# RTC.net
KiCad netlist of a schematic drawn in EAGLE
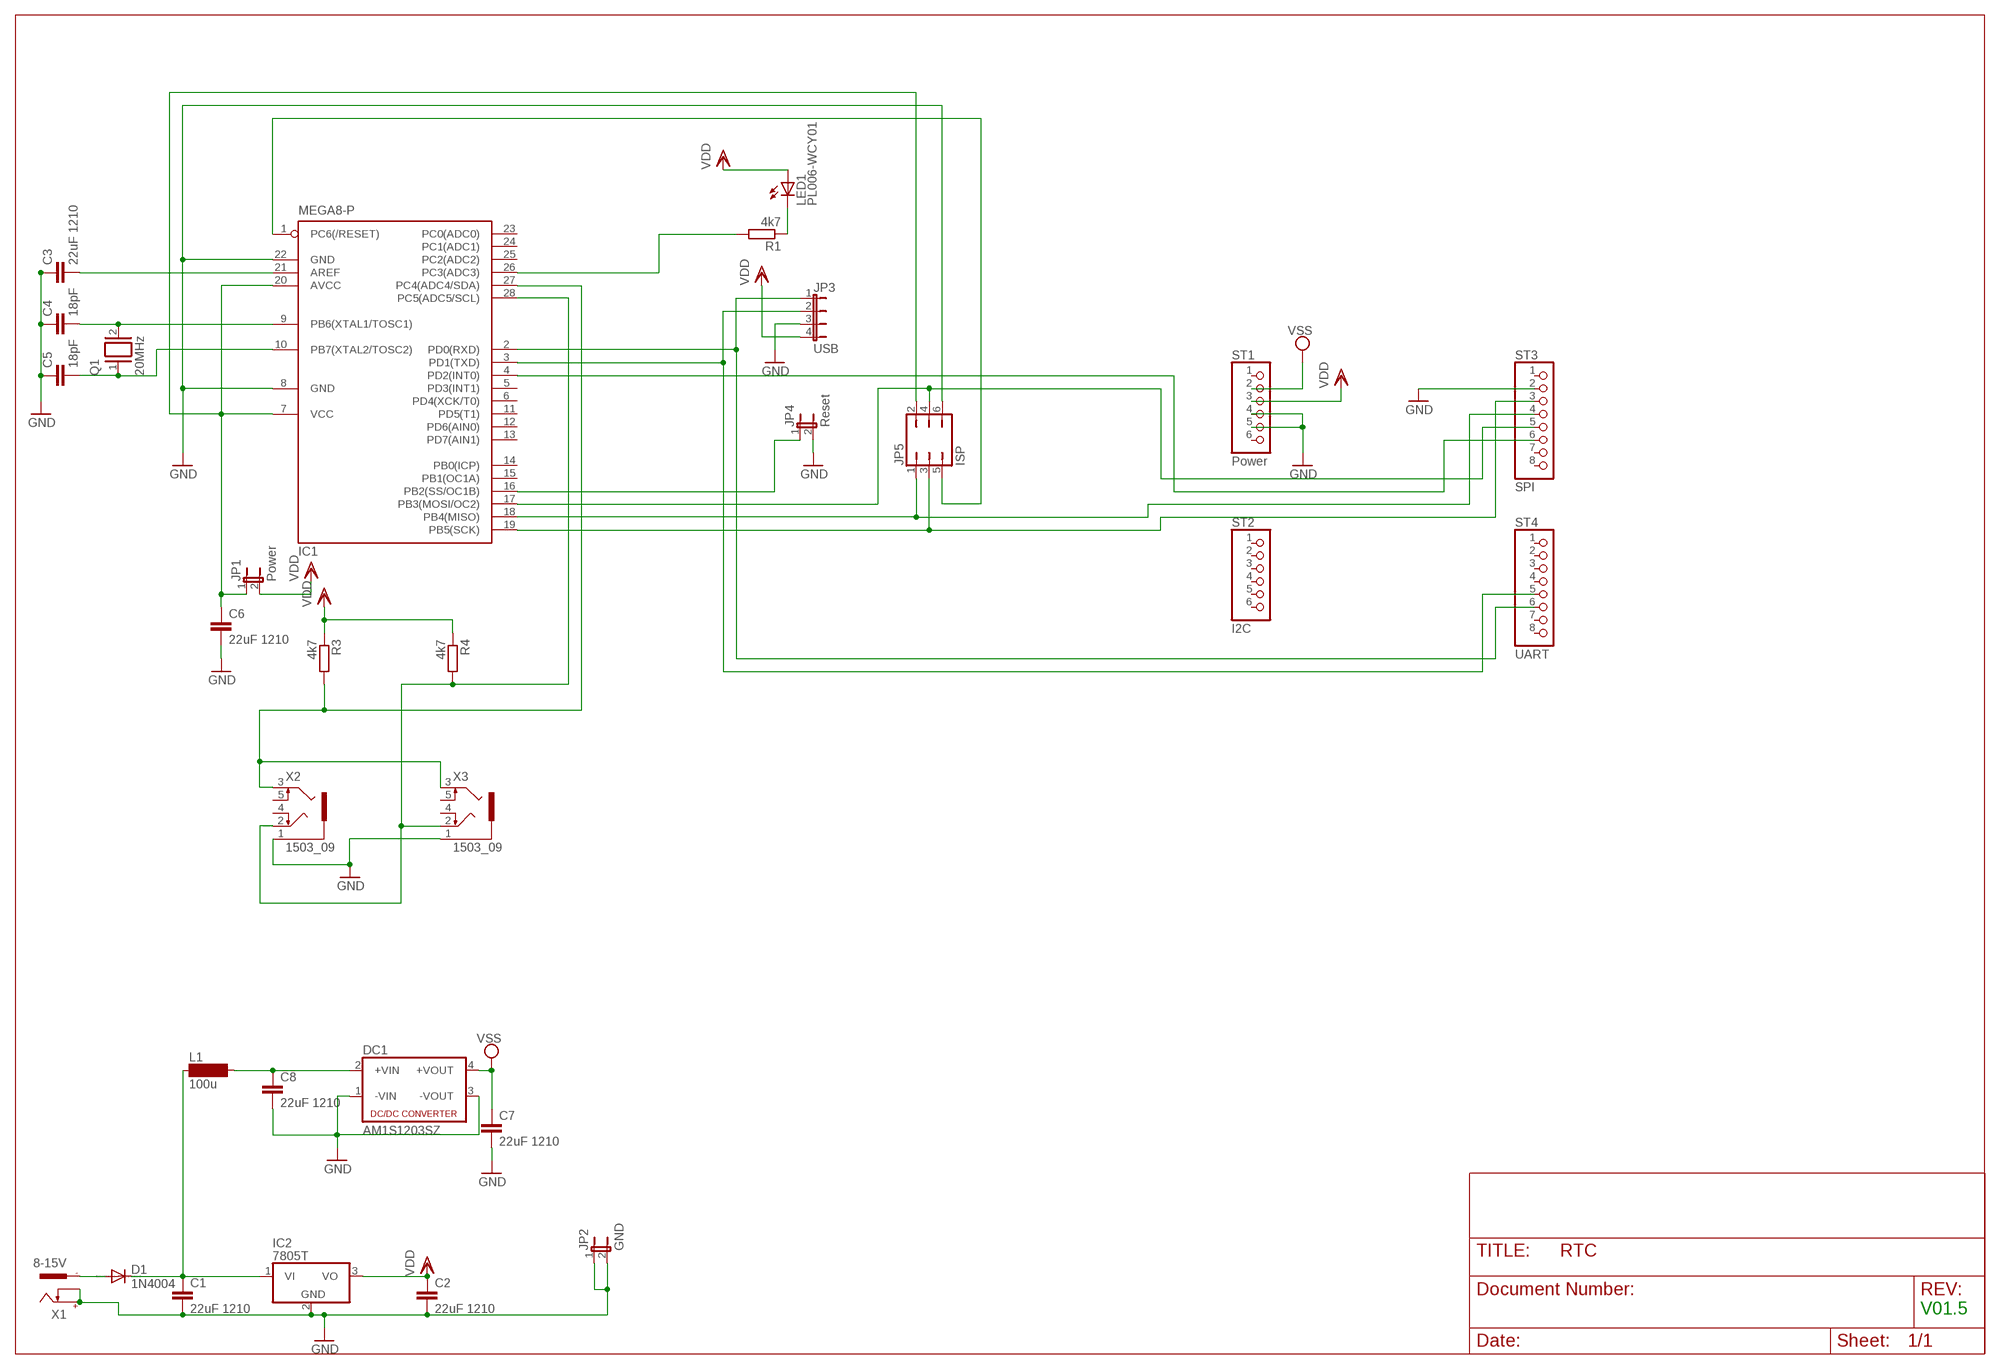
[diagram p0: schematic, sheet 1]

(export (version "E")
  (design (tool "Eeschema 10.0.6"))
  (components
    (comp (ref "C1")
      (value "22uF 1210")
      (footprint "eagle-import:C1206")
      (libsource (lib "eagle-import") (part "C-EUC1206"))
    )
    (comp (ref "C2")
      (value "22uF 1210")
      (footprint "eagle-import:C1206")
      (libsource (lib "eagle-import") (part "C-EUC1206"))
    )
    (comp (ref "C3")
      (value "22uF 1210")
      (footprint "eagle-import:C1206")
      (libsource (lib "eagle-import") (part "C-EUC1206"))
    )
    (comp (ref "C4")
      (value "18pF")
      (footprint "eagle-import:C025-025X050")
      (libsource (lib "eagle-import") (part "resistor_C-EU025-025X050"))
    )
    (comp (ref "C5")
      (value "18pF")
      (footprint "eagle-import:C025-025X050")
      (libsource (lib "eagle-import") (part "resistor_C-EU025-025X050"))
    )
    (comp (ref "C6")
      (value "22uF 1210")
      (footprint "eagle-import:C1206")
      (libsource (lib "eagle-import") (part "C-EUC1206"))
    )
    (comp (ref "C7")
      (value "22uF 1210")
      (footprint "eagle-import:C1206")
      (libsource (lib "eagle-import") (part "C-EUC1206"))
    )
    (comp (ref "C8")
      (value "22uF 1210")
      (footprint "eagle-import:C1206")
      (libsource (lib "eagle-import") (part "C-EUC1206"))
    )
    (comp (ref "D1")
      (value "1N4004")
      (footprint "eagle-import:DO41-10")
      (libsource (lib "eagle-import") (part "1N4004"))
    )
    (comp (ref "DC1")
      (value "AM1S1203SZ")
      (footprint "eagle-import:NME")
      (fields (field (name "MF") "C & D TECHNOLOGIES, INC") (field (name "MPN") "NME1205D"))
      (libsource (lib "eagle-import") (part "NME"))
    )
    (comp (ref "IC1")
      (value "MEGA8-P")
      (footprint "eagle-import:DIL28-3")
      (libsource (lib "eagle-import") (part "MEGA8-P"))
    )
    (comp (ref "IC2")
      (value "7805T")
      (footprint "eagle-import:TO220H")
      (libsource (lib "eagle-import") (part "78T05"))
    )
    (comp (ref "JP1")
      (value "Power")
      (footprint "eagle-import:JP1")
      (libsource (lib "eagle-import") (part "JP1E"))
    )
    (comp (ref "JP2")
      (value "GND")
      (footprint "eagle-import:JP1")
      (libsource (lib "eagle-import") (part "JP1E"))
    )
    (comp (ref "JP3")
      (value "USB")
      (footprint "eagle-import:JP4")
      (libsource (lib "eagle-import") (part "JP4E"))
    )
    (comp (ref "JP4")
      (value "Reset")
      (footprint "eagle-import:JP1")
      (libsource (lib "eagle-import") (part "JP1E"))
    )
    (comp (ref "JP5")
      (value "ISP")
      (footprint "eagle-import:JP3Q")
      (libsource (lib "eagle-import") (part "JP3Q"))
    )
    (comp (ref "L1")
      (value "100u")
      (footprint "eagle-import:MS85")
      (libsource (lib "eagle-import") (part "MS85"))
    )
    (comp (ref "LED1")
      (value "PL006-WCY01")
      (footprint "eagle-import:SOT23")
      (libsource (lib "eagle-import") (part "PL006-WCY01"))
    )
    (comp (ref "Q1")
      (value "20MHz")
      (footprint "eagle-import:QS")
      (libsource (lib "eagle-import") (part "XTAL/S"))
    )
    (comp (ref "R1")
      (value "4k7")
      (footprint "eagle-import:M1206")
      (libsource (lib "eagle-import") (part "R-EU_M1206"))
    )
    (comp (ref "R3")
      (value "4k7")
      (footprint "eagle-import:R1206")
      (libsource (lib "eagle-import") (part "R-EU_R1206"))
    )
    (comp (ref "R4")
      (value "4k7")
      (footprint "eagle-import:R1206")
      (libsource (lib "eagle-import") (part "R-EU_R1206"))
    )
    (comp (ref "ST1")
      (value "Power")
      (footprint "eagle-import:1X06")
      (libsource (lib "eagle-import") (part "PINHD-1X6"))
    )
    (comp (ref "ST2")
      (value "I2C")
      (footprint "eagle-import:1X06")
      (libsource (lib "eagle-import") (part "PINHD-1X6"))
    )
    (comp (ref "ST3")
      (value "SPI")
      (footprint "eagle-import:1X08")
      (libsource (lib "eagle-import") (part "PINHD-1X8"))
    )
    (comp (ref "ST4")
      (value "UART")
      (footprint "eagle-import:1X08")
      (libsource (lib "eagle-import") (part "PINHD-1X8"))
    )
    (comp (ref "X1")
      (value "8-15V")
      (footprint "eagle-import:737992-5")
      (libsource (lib "eagle-import") (part "737992-55"))
    )
    (comp (ref "X2")
      (value "1503_09")
      (footprint "eagle-import:1503_09")
      (libsource (lib "eagle-import") (part "1503_09"))
    )
    (comp (ref "X3")
      (value "1503_09")
      (footprint "eagle-import:1503_09")
      (libsource (lib "eagle-import") (part "1503_09"))
    )
  )
  (nets
    (net (code "1") (name "GND") (class "Default")
      (node (ref "C1") (pin "2") (pinfunction "2_2") (pintype "passive"))
      (node (ref "C2") (pin "2") (pinfunction "2_2") (pintype "passive"))
      (node (ref "C3") (pin "1") (pinfunction "1_1") (pintype "passive"))
      (node (ref "C4") (pin "1") (pinfunction "1_1") (pintype "passive"))
      (node (ref "C5") (pin "1") (pinfunction "1_1") (pintype "passive"))
      (node (ref "C6") (pin "2") (pinfunction "2_2") (pintype "passive"))
      (node (ref "C7") (pin "2") (pinfunction "2_2") (pintype "passive"))
      (node (ref "C8") (pin "2") (pinfunction "2_2") (pintype "passive"))
      (node (ref "DC1") (pin "1") (pinfunction "-VIN_1") (pintype "passive"))
      (node (ref "DC1") (pin "3") (pinfunction "-VOUT_3") (pintype "passive"))
      (node (ref "IC1") (pin "22") (pinfunction "GND_22") (pintype "power_in"))
      (node (ref "IC1") (pin "8") (pinfunction "GND_8") (pintype "power_in"))
      (node (ref "IC2") (pin "2") (pinfunction "GND_2") (pintype "passive"))
      (node (ref "JP2") (pin "1") (pinfunction "1_1") (pintype "passive"))
      (node (ref "JP2") (pin "2") (pinfunction "2_2") (pintype "passive"))
      (node (ref "JP3") (pin "3") (pinfunction "3_3") (pintype "passive"))
      (node (ref "JP4") (pin "2") (pinfunction "2_2") (pintype "passive"))
      (node (ref "JP5") (pin "6") (pinfunction "6_6") (pintype "passive"))
      (node (ref "ST1") (pin "4") (pinfunction "4_4") (pintype "passive"))
      (node (ref "ST1") (pin "5") (pinfunction "5_5") (pintype "passive"))
      (node (ref "ST3") (pin "2") (pinfunction "2_2") (pintype "passive"))
      (node (ref "X1") (pin "+") (pinfunction "+_+") (pintype "passive"))
      (node (ref "X1") (pin "K") (pinfunction "K_K") (pintype "passive"))
      (node (ref "X2") (pin "1") (pinfunction "1_1") (pintype "passive"))
      (node (ref "X3") (pin "1") (pinfunction "1_1") (pintype "passive"))
    )
    (net (code "2") (name "Net-(D1-PadA)") (class "Default")
      (node (ref "D1") (pin "A") (pinfunction "A_A") (pintype "passive"))
      (node (ref "X1") (pin "-1") (pinfunction "-1_-1") (pintype "passive"))
    )
    (net (code "3") (name "Net-(DC1-+VIN)") (class "Default")
      (node (ref "C8") (pin "1") (pinfunction "1_1") (pintype "passive"))
      (node (ref "DC1") (pin "2") (pinfunction "+VIN_2") (pintype "passive"))
      (node (ref "L1") (pin "2") (pinfunction "2_2") (pintype "passive"))
    )
    (net (code "4") (name "Net-(IC1-AREF)") (class "Default")
      (node (ref "C3") (pin "2") (pinfunction "2_2") (pintype "passive"))
      (node (ref "IC1") (pin "21") (pinfunction "AREF_21") (pintype "passive"))
    )
    (net (code "5") (name "Net-(IC1-AVCC)") (class "Default")
      (node (ref "C6") (pin "1") (pinfunction "1_1") (pintype "passive"))
      (node (ref "IC1") (pin "20") (pinfunction "AVCC_20") (pintype "power_in"))
      (node (ref "IC1") (pin "7") (pinfunction "VCC_7") (pintype "power_in"))
      (node (ref "JP1") (pin "1") (pinfunction "1_1") (pintype "passive"))
      (node (ref "JP5") (pin "2") (pinfunction "2_2") (pintype "passive"))
    )
    (net (code "6") (name "Net-(IC1-PB2(SS{slash}OC1B))") (class "Default")
      (node (ref "IC1") (pin "16") (pinfunction "PB2(SS/OC1B)_16") (pintype "bidirectional"))
      (node (ref "JP4") (pin "1") (pinfunction "1_1") (pintype "passive"))
    )
    (net (code "7") (name "Net-(IC1-PB3(MOSI{slash}OC2))") (class "Default")
      (node (ref "IC1") (pin "17") (pinfunction "PB3(MOSI/OC2)_17") (pintype "bidirectional"))
      (node (ref "JP5") (pin "4") (pinfunction "4_4") (pintype "passive"))
      (node (ref "ST3") (pin "5") (pinfunction "5_5") (pintype "passive"))
    )
    (net (code "8") (name "Net-(IC1-PB4(MISO))") (class "Default")
      (node (ref "IC1") (pin "18") (pinfunction "PB4(MISO)_18") (pintype "bidirectional"))
      (node (ref "JP5") (pin "1") (pinfunction "1_1") (pintype "passive"))
      (node (ref "ST3") (pin "4") (pinfunction "4_4") (pintype "passive"))
    )
    (net (code "9") (name "Net-(IC1-PB5(SCK))") (class "Default")
      (node (ref "IC1") (pin "19") (pinfunction "PB5(SCK)_19") (pintype "bidirectional"))
      (node (ref "JP5") (pin "3") (pinfunction "3_3") (pintype "passive"))
      (node (ref "ST3") (pin "3") (pinfunction "3_3") (pintype "passive"))
    )
    (net (code "10") (name "Net-(IC1-PB6(XTAL1{slash}TOSC1))") (class "Default")
      (node (ref "C4") (pin "2") (pinfunction "2_2") (pintype "passive"))
      (node (ref "IC1") (pin "9") (pinfunction "PB6(XTAL1/TOSC1)_9") (pintype "bidirectional"))
      (node (ref "Q1") (pin "2") (pinfunction "2_2") (pintype "passive"))
    )
    (net (code "11") (name "Net-(IC1-PB7(XTAL2{slash}TOSC2))") (class "Default")
      (node (ref "C5") (pin "2") (pinfunction "2_2") (pintype "passive"))
      (node (ref "IC1") (pin "10") (pinfunction "PB7(XTAL2/TOSC2)_10") (pintype "bidirectional"))
      (node (ref "Q1") (pin "1") (pinfunction "1_1") (pintype "passive"))
    )
    (net (code "12") (name "Net-(IC1-PC3(ADC3))") (class "Default")
      (node (ref "IC1") (pin "26") (pinfunction "PC3(ADC3)_26") (pintype "bidirectional"))
      (node (ref "R1") (pin "2") (pinfunction "2_2") (pintype "passive"))
    )
    (net (code "13") (name "Net-(IC1-PC4(ADC4{slash}SDA))") (class "Default")
      (node (ref "IC1") (pin "27") (pinfunction "PC4(ADC4/SDA)_27") (pintype "bidirectional"))
      (node (ref "R3") (pin "2") (pinfunction "2_2") (pintype "passive"))
      (node (ref "X2") (pin "3") (pinfunction "3_3") (pintype "passive"))
      (node (ref "X3") (pin "3") (pinfunction "3_3") (pintype "passive"))
    )
    (net (code "14") (name "Net-(IC1-PC5(ADC5{slash}SCL))") (class "Default")
      (node (ref "IC1") (pin "28") (pinfunction "PC5(ADC5/SCL)_28") (pintype "bidirectional"))
      (node (ref "R4") (pin "2") (pinfunction "2_2") (pintype "passive"))
      (node (ref "X2") (pin "2") (pinfunction "2_2") (pintype "passive"))
      (node (ref "X3") (pin "2") (pinfunction "2_2") (pintype "passive"))
    )
    (net (code "15") (name "Net-(IC1-PC6({slash}RESET))") (class "Default")
      (node (ref "IC1") (pin "1") (pinfunction "PC6(/RESET)_1") (pintype "bidirectional"))
      (node (ref "JP5") (pin "5") (pinfunction "5_5") (pintype "passive"))
    )
    (net (code "16") (name "Net-(IC1-PD0(RXD))") (class "Default")
      (node (ref "IC1") (pin "2") (pinfunction "PD0(RXD)_2") (pintype "bidirectional"))
      (node (ref "JP3") (pin "1") (pinfunction "1_1") (pintype "passive"))
      (node (ref "ST4") (pin "6") (pinfunction "6_6") (pintype "passive"))
    )
    (net (code "17") (name "Net-(IC1-PD1(TXD))") (class "Default")
      (node (ref "IC1") (pin "3") (pinfunction "PD1(TXD)_3") (pintype "bidirectional"))
      (node (ref "JP3") (pin "2") (pinfunction "2_2") (pintype "passive"))
      (node (ref "ST4") (pin "5") (pinfunction "5_5") (pintype "passive"))
    )
    (net (code "18") (name "Net-(IC1-PD2(INT0))") (class "Default")
      (node (ref "IC1") (pin "4") (pinfunction "PD2(INT0)_4") (pintype "bidirectional"))
      (node (ref "ST3") (pin "6") (pinfunction "6_6") (pintype "passive"))
    )
    (net (code "19") (name "Net-(IC2-VI)") (class "Default")
      (node (ref "C1") (pin "1") (pinfunction "1_1") (pintype "passive"))
      (node (ref "D1") (pin "C") (pinfunction "C_C") (pintype "passive"))
      (node (ref "IC2") (pin "1") (pinfunction "VI_1") (pintype "input"))
      (node (ref "L1") (pin "1") (pinfunction "1_1") (pintype "passive"))
    )
    (net (code "20") (name "Net-(LED1-C)") (class "Default")
      (node (ref "LED1") (pin "3") (pinfunction "C_3") (pintype "passive"))
      (node (ref "R1") (pin "1") (pinfunction "1_1") (pintype "passive"))
    )
    (net (code "21") (name "VDD") (class "Default")
      (node (ref "C2") (pin "1") (pinfunction "1_1") (pintype "passive"))
      (node (ref "IC2") (pin "3") (pinfunction "VO_3") (pintype "passive"))
      (node (ref "JP1") (pin "2") (pinfunction "2_2") (pintype "passive"))
      (node (ref "JP3") (pin "4") (pinfunction "4_4") (pintype "passive"))
      (node (ref "LED1") (pin "1") (pinfunction "A_1") (pintype "passive"))
      (node (ref "R3") (pin "1") (pinfunction "1_1") (pintype "passive"))
      (node (ref "R4") (pin "1") (pinfunction "1_1") (pintype "passive"))
      (node (ref "ST1") (pin "3") (pinfunction "3_3") (pintype "passive"))
    )
    (net (code "22") (name "VSS") (class "Default")
      (node (ref "C7") (pin "1") (pinfunction "1_1") (pintype "passive"))
      (node (ref "DC1") (pin "4") (pinfunction "+VOUT_4") (pintype "passive"))
      (node (ref "ST1") (pin "2") (pinfunction "2_2") (pintype "passive"))
    )
    (net (code "23") (name "unconnected-(IC1-PB0(ICP)-Pad14)") (class "Default")
      (node (ref "IC1") (pin "14") (pinfunction "PB0(ICP)_14") (pintype "bidirectional"))
    )
    (net (code "24") (name "unconnected-(IC1-PB1(OC1A)-Pad15)") (class "Default")
      (node (ref "IC1") (pin "15") (pinfunction "PB1(OC1A)_15") (pintype "bidirectional"))
    )
    (net (code "25") (name "unconnected-(IC1-PC0(ADC0)-Pad23)") (class "Default")
      (node (ref "IC1") (pin "23") (pinfunction "PC0(ADC0)_23") (pintype "bidirectional"))
    )
    (net (code "26") (name "unconnected-(IC1-PC1(ADC1)-Pad24)") (class "Default")
      (node (ref "IC1") (pin "24") (pinfunction "PC1(ADC1)_24") (pintype "bidirectional"))
    )
    (net (code "27") (name "unconnected-(IC1-PC2(ADC2)-Pad25)") (class "Default")
      (node (ref "IC1") (pin "25") (pinfunction "PC2(ADC2)_25") (pintype "bidirectional"))
    )
    (net (code "28") (name "unconnected-(IC1-PD3(INT1)-Pad5)") (class "Default")
      (node (ref "IC1") (pin "5") (pinfunction "PD3(INT1)_5") (pintype "bidirectional"))
    )
    (net (code "29") (name "unconnected-(IC1-PD4(XCK{slash}T0)-Pad6)") (class "Default")
      (node (ref "IC1") (pin "6") (pinfunction "PD4(XCK/T0)_6") (pintype "bidirectional"))
    )
    (net (code "30") (name "unconnected-(IC1-PD5(T1)-Pad11)") (class "Default")
      (node (ref "IC1") (pin "11") (pinfunction "PD5(T1)_11") (pintype "bidirectional"))
    )
    (net (code "31") (name "unconnected-(IC1-PD6(AIN0)-Pad12)") (class "Default")
      (node (ref "IC1") (pin "12") (pinfunction "PD6(AIN0)_12") (pintype "bidirectional"))
    )
    (net (code "32") (name "unconnected-(IC1-PD7(AIN1)-Pad13)") (class "Default")
      (node (ref "IC1") (pin "13") (pinfunction "PD7(AIN1)_13") (pintype "bidirectional"))
    )
    (net (code "33") (name "unconnected-(ST1-Pad1)") (class "Default")
      (node (ref "ST1") (pin "1") (pinfunction "1_1") (pintype "passive"))
    )
    (net (code "34") (name "unconnected-(ST1-Pad6)") (class "Default")
      (node (ref "ST1") (pin "6") (pinfunction "6_6") (pintype "passive"))
    )
    (net (code "35") (name "unconnected-(ST2-Pad1)") (class "Default")
      (node (ref "ST2") (pin "1") (pinfunction "1_1") (pintype "passive"))
    )
    (net (code "36") (name "unconnected-(ST2-Pad2)") (class "Default")
      (node (ref "ST2") (pin "2") (pinfunction "2_2") (pintype "passive"))
    )
    (net (code "37") (name "unconnected-(ST2-Pad3)") (class "Default")
      (node (ref "ST2") (pin "3") (pinfunction "3_3") (pintype "passive"))
    )
    (net (code "38") (name "unconnected-(ST2-Pad4)") (class "Default")
      (node (ref "ST2") (pin "4") (pinfunction "4_4") (pintype "passive"))
    )
    (net (code "39") (name "unconnected-(ST2-Pad5)") (class "Default")
      (node (ref "ST2") (pin "5") (pinfunction "5_5") (pintype "passive"))
    )
    (net (code "40") (name "unconnected-(ST2-Pad6)") (class "Default")
      (node (ref "ST2") (pin "6") (pinfunction "6_6") (pintype "passive"))
    )
    (net (code "41") (name "unconnected-(ST3-Pad1)") (class "Default")
      (node (ref "ST3") (pin "1") (pinfunction "1_1") (pintype "passive"))
    )
    (net (code "42") (name "unconnected-(ST3-Pad7)") (class "Default")
      (node (ref "ST3") (pin "7") (pinfunction "7_7") (pintype "passive"))
    )
    (net (code "43") (name "unconnected-(ST3-Pad8)") (class "Default")
      (node (ref "ST3") (pin "8") (pinfunction "8_8") (pintype "passive"))
    )
    (net (code "44") (name "unconnected-(ST4-Pad1)") (class "Default")
      (node (ref "ST4") (pin "1") (pinfunction "1_1") (pintype "passive"))
    )
    (net (code "45") (name "unconnected-(ST4-Pad2)") (class "Default")
      (node (ref "ST4") (pin "2") (pinfunction "2_2") (pintype "passive"))
    )
    (net (code "46") (name "unconnected-(ST4-Pad3)") (class "Default")
      (node (ref "ST4") (pin "3") (pinfunction "3_3") (pintype "passive"))
    )
    (net (code "47") (name "unconnected-(ST4-Pad4)") (class "Default")
      (node (ref "ST4") (pin "4") (pinfunction "4_4") (pintype "passive"))
    )
    (net (code "48") (name "unconnected-(ST4-Pad7)") (class "Default")
      (node (ref "ST4") (pin "7") (pinfunction "7_7") (pintype "passive"))
    )
    (net (code "49") (name "unconnected-(ST4-Pad8)") (class "Default")
      (node (ref "ST4") (pin "8") (pinfunction "8_8") (pintype "passive"))
    )
    (net (code "50") (name "unconnected-(X1-Pad-2)") (class "Default")
      (node (ref "X1") (pin "-2") (pinfunction "-2_-2") (pintype "passive"))
    )
    (net (code "51") (name "unconnected-(X2-Pad4)") (class "Default")
      (node (ref "X2") (pin "4") (pinfunction "4_4") (pintype "passive"))
    )
    (net (code "52") (name "unconnected-(X2-Pad5)") (class "Default")
      (node (ref "X2") (pin "5") (pinfunction "5_5") (pintype "passive"))
    )
    (net (code "53") (name "unconnected-(X3-Pad4)") (class "Default")
      (node (ref "X3") (pin "4") (pinfunction "4_4") (pintype "passive"))
    )
    (net (code "54") (name "unconnected-(X3-Pad5)") (class "Default")
      (node (ref "X3") (pin "5") (pinfunction "5_5") (pintype "passive"))
    )
  )
)
